# Hafidin_Alfath_GT.net
KiCad netlist of a schematic drawn in EAGLE
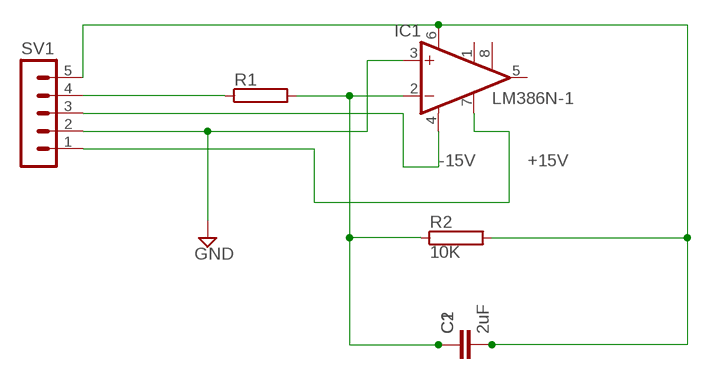
[diagram p0: schematic, sheet 1]

(export (version "E")
  (design (tool "Eeschema 10.0.6"))
  (components
    (comp (ref "C1")
      (value "C-EU025-024X044")
      (footprint "eagle-import:C025-024X044")
      (libsource (lib "eagle-import") (part "C-EU025-024X044"))
    )
    (comp (ref "C2")
      (value "2uF")
      (footprint "eagle-import:C025-024X044")
      (libsource (lib "eagle-import") (part "C-EU025-024X044"))
    )
    (comp (ref "IC1")
      (value "LM386N-1")
      (footprint "eagle-import:DIL08")
      (libsource (lib "eagle-import") (part "LM386?-N1"))
    )
    (comp (ref "R1")
      (value "RCA5050")
      (footprint "eagle-import:CA5050")
      (libsource (lib "eagle-import") (part "RCA5050"))
    )
    (comp (ref "R2")
      (value "10K")
      (footprint "eagle-import:CA5050")
      (libsource (lib "eagle-import") (part "RCA5050"))
    )
    (comp (ref "SV1")
      (value "MA05-1")
      (footprint "eagle-import:MA05-1")
      (libsource (lib "eagle-import") (part "MA05-1"))
    )
  )
  (nets
    (net (code "1") (name "/+15V") (class "Default")
      (node (ref "IC1") (pin "7") (pinfunction "BYPASS_7") (pintype "passive"))
      (node (ref "SV1") (pin "1") (pinfunction "1_1") (pintype "passive"))
    )
    (net (code "2") (name "/-15V") (class "Default")
      (node (ref "IC1") (pin "4") (pinfunction "GND_4") (pintype "power_in"))
      (node (ref "SV1") (pin "3") (pinfunction "3_3") (pintype "passive"))
    )
    (net (code "3") (name "GND") (class "Default")
      (node (ref "IC1") (pin "3") (pinfunction "+IN_3") (pintype "input"))
      (node (ref "SV1") (pin "2") (pinfunction "2_2") (pintype "passive"))
    )
    (net (code "4") (name "Net-(IC1--IN)") (class "Default")
      (node (ref "C1") (pin "1") (pinfunction "1_1") (pintype "passive"))
      (node (ref "C2") (pin "1") (pinfunction "1_1") (pintype "passive"))
      (node (ref "IC1") (pin "2") (pinfunction "-IN_2") (pintype "input"))
      (node (ref "R1") (pin "2") (pinfunction "2_2") (pintype "passive"))
      (node (ref "R2") (pin "1") (pinfunction "1_1") (pintype "passive"))
    )
    (net (code "5") (name "Net-(IC1-VS)") (class "Default")
      (node (ref "C1") (pin "2") (pinfunction "2_2") (pintype "passive"))
      (node (ref "C2") (pin "2") (pinfunction "2_2") (pintype "passive"))
      (node (ref "IC1") (pin "6") (pinfunction "VS_6") (pintype "power_in"))
      (node (ref "R2") (pin "2") (pinfunction "2_2") (pintype "passive"))
      (node (ref "SV1") (pin "5") (pinfunction "5_5") (pintype "passive"))
    )
    (net (code "6") (name "Net-(R1-Pad1)") (class "Default")
      (node (ref "R1") (pin "1") (pinfunction "1_1") (pintype "passive"))
      (node (ref "SV1") (pin "4") (pinfunction "4_4") (pintype "passive"))
    )
    (net (code "7") (name "unconnected-(IC1-GAIN-Pad1)") (class "Default")
      (node (ref "IC1") (pin "1") (pinfunction "GAIN_1") (pintype "passive"))
    )
    (net (code "8") (name "unconnected-(IC1-GAIN-Pad8)") (class "Default")
      (node (ref "IC1") (pin "8") (pinfunction "GAIN_8") (pintype "passive"))
    )
    (net (code "9") (name "unconnected-(IC1-OUT-Pad5)") (class "Default")
      (node (ref "IC1") (pin "5") (pinfunction "OUT_5") (pintype "output"))
    )
  )
)
